# 04_MCU-Part1.net
KiCad netlist of a schematic drawn in Altium Designer
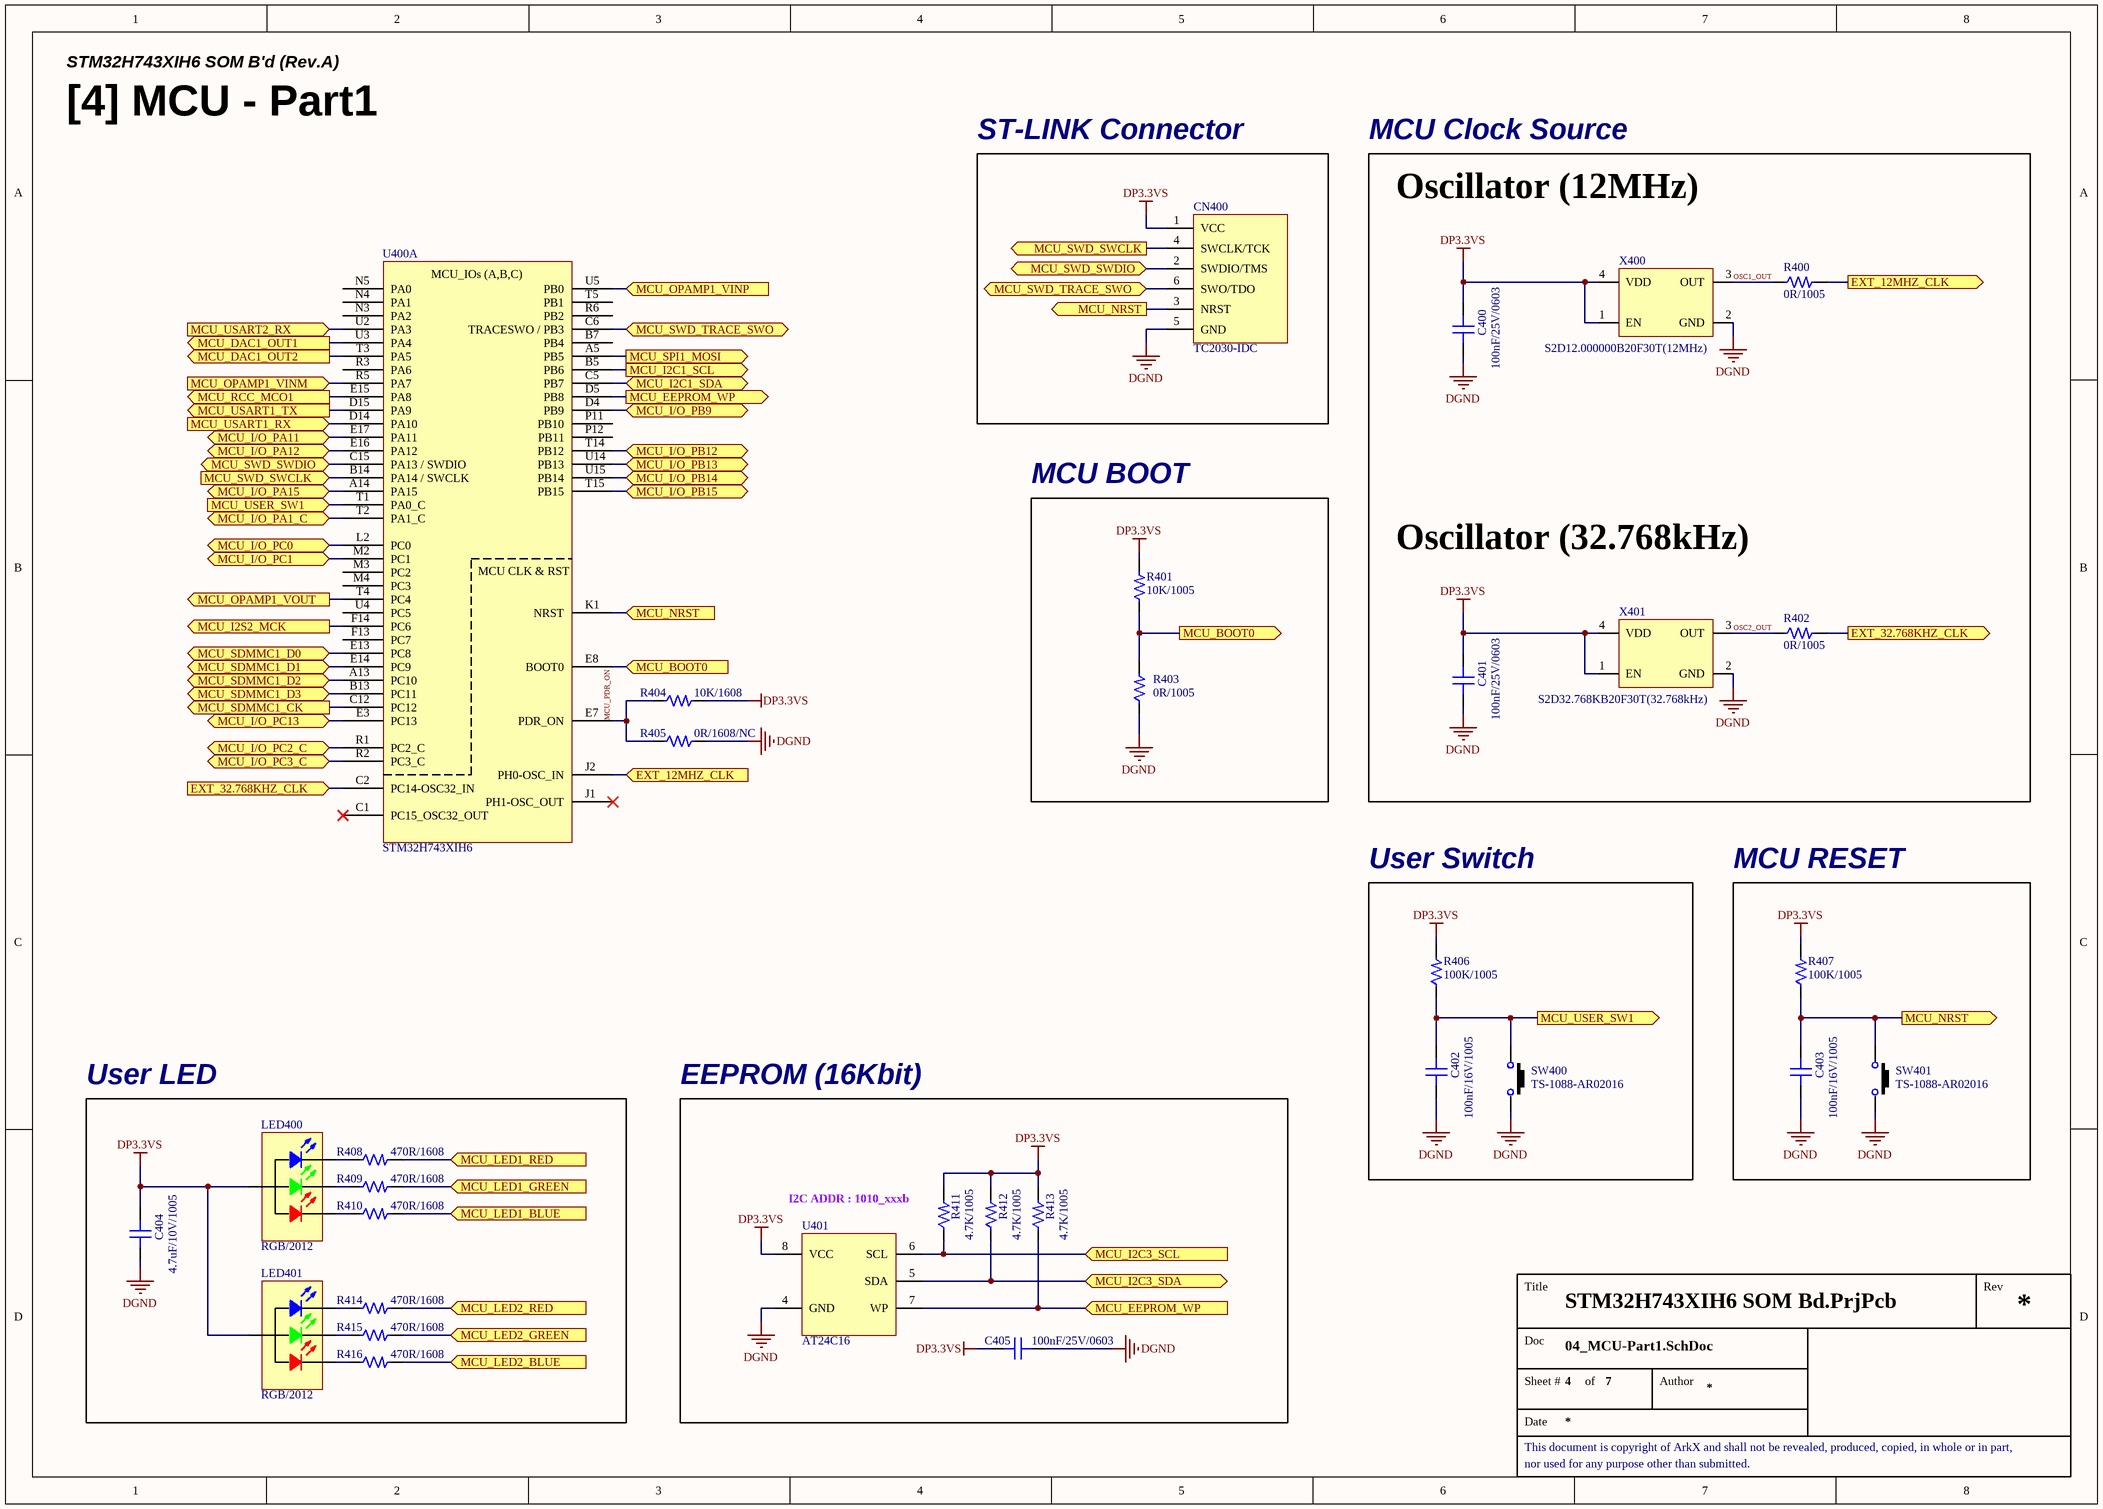
[diagram p0: 04_MCU-Part1.SchDoc]

(export (version "E")
  (design (tool "Eeschema 10.0.6"))
  (components
    (comp (ref "C400")
      (value "100nF/25V/0603")
      (footprint "CAP 0603 (0201_INCH)")
      (description "Ceramic CAP_100nF/25V/0603")
      (fields (field (name "LCSC PART #") "C181047"))
      (libsource (lib "Arkx") (part "CAP_100nF/25V/0603"))
    )
    (comp (ref "C401")
      (value "100nF/25V/0603")
      (footprint "CAP 0603 (0201_INCH)")
      (description "Ceramic CAP_100nF/25V/0603")
      (fields (field (name "LCSC PART #") "C181047"))
      (libsource (lib "Arkx") (part "CAP_100nF/25V/0603"))
    )
    (comp (ref "C402")
      (value "100nF/16V/1005")
      (footprint "CAP 1005 (0402_INCH)")
      (description "Ceramic CAP_100nF/16V/1005")
      (fields (field (name "LCSC PART #") "C1525"))
      (libsource (lib "Arkx") (part "CAP_100nF/16V/1005"))
    )
    (comp (ref "C403")
      (value "100nF/16V/1005")
      (footprint "CAP 1005 (0402_INCH)")
      (description "Ceramic CAP_100nF/16V/1005")
      (fields (field (name "LCSC PART #") "C1525"))
      (libsource (lib "Arkx") (part "CAP_100nF/16V/1005"))
    )
    (comp (ref "C404")
      (value "4.7uF/10V/1005")
      (footprint "CAP 1005 (0402_INCH)")
      (description "10V 4.7uF X5R ±20% 0402  Multilayer Ceramic Capacitors MLCC - SMD/SMT ROHS")
      (fields (field (name "LCSC PART #") "C23733"))
      (libsource (lib "Arkx") (part "CAP_4.7uF/10V/1005"))
    )
    (comp (ref "C405")
      (value "100nF/25V/0603")
      (footprint "CAP 0603 (0201_INCH)")
      (description "Ceramic CAP_100nF/25V/0603")
      (fields (field (name "LCSC PART #") "C181047"))
      (libsource (lib "Arkx") (part "CAP_100nF/25V/0603"))
    )
    (comp (ref "CN400")
      (value "TC2030-IDC")
      (footprint "CON_TC2030-FP")
      (description "Tag-Connect No-Solder SWD Debug Connector DO NOT PLACE")
      (fields (field (name "MANUFACTURER") "Tag-Connect") (field (name "MANUFACTURER PART NUMBER") "TC2030"))
      (libsource (lib "Arkx") (part "CON_TC2030-IDC"))
    )
    (comp (ref "LED400")
      (value "RGB/2012")
      (footprint "LED MHT170RGBCT")
      (fields (field (name "LCSC PART #") "C2962094"))
      (libsource (lib "Arkx") (part "LED_RGB_MHT170RGBCT"))
    )
    (comp (ref "LED401")
      (value "RGB/2012")
      (footprint "LED MHT170RGBCT")
      (fields (field (name "LCSC PART #") "C2962094"))
      (libsource (lib "Arkx") (part "LED_RGB_MHT170RGBCT"))
    )
    (comp (ref "R400")
      (value "0R/1005")
      (footprint "RES 1005 (0402_inch)")
      (description "RES_0R/1005/62.5mW")
      (fields (field (name "LCSC PART #") "C17168"))
      (libsource (lib "Arkx") (part "RES_0R/1005/62.5mW"))
    )
    (comp (ref "R401")
      (value "10K/1005")
      (footprint "RES 1005 (0402_inch)")
      (description "RES_10K/1005/62.5mW")
      (fields (field (name "LCSC PART #") "C25744"))
      (libsource (lib "Arkx") (part "RES_10K/1005/62.5mW"))
    )
    (comp (ref "R402")
      (value "0R/1005")
      (footprint "RES 1005 (0402_inch)")
      (description "RES_0R/1005/62.5mW")
      (fields (field (name "LCSC PART #") "C17168"))
      (libsource (lib "Arkx") (part "RES_0R/1005/62.5mW"))
    )
    (comp (ref "R403")
      (value "0R/1005")
      (footprint "RES 1005 (0402_inch)")
      (description "RES_0R/1005/62.5mW")
      (fields (field (name "LCSC PART #") "C17168"))
      (libsource (lib "Arkx") (part "RES_0R/1005/62.5mW"))
    )
    (comp (ref "R404")
      (value "10K/1608")
      (footprint "RES 1608 (0603_inch)")
      (description "RES_10K/1608/0.1W")
      (fields (field (name "LCSC PART #") "C25804"))
      (libsource (lib "Arkx") (part "RES_10K/1608/0.1W"))
    )
    (comp (ref "R405")
      (value "0R/1608/NC")
      (footprint "RES 1608 (0603_inch)/NC")
      (description "0R/1608/0.1W/NC")
      (libsource (lib "Arkx") (part "RES_NC_0R/1608/0.1W"))
    )
    (comp (ref "R406")
      (value "100K/1005")
      (footprint "RES 1005 (0402_inch)")
      (description "RES_100K/1005/62.5mW")
      (fields (field (name "LCSC PART #") "C25741"))
      (libsource (lib "Arkx") (part "RES_100K/1005/62.5mW"))
    )
    (comp (ref "R407")
      (value "100K/1005")
      (footprint "RES 1005 (0402_inch)")
      (description "RES_100K/1005/62.5mW")
      (fields (field (name "LCSC PART #") "C25741"))
      (libsource (lib "Arkx") (part "RES_100K/1005/62.5mW"))
    )
    (comp (ref "R408")
      (value "470R/1608")
      (footprint "RES 1608 (0603_inch)")
      (description "RES_470R/1608/0.1W")
      (fields (field (name "LCSC PART #") "C23179"))
      (libsource (lib "Arkx") (part "RES_470R/1608/0.1W"))
    )
    (comp (ref "R409")
      (value "470R/1608")
      (footprint "RES 1608 (0603_inch)")
      (description "RES_470R/1608/0.1W")
      (fields (field (name "LCSC PART #") "C23179"))
      (libsource (lib "Arkx") (part "RES_470R/1608/0.1W"))
    )
    (comp (ref "R410")
      (value "470R/1608")
      (footprint "RES 1608 (0603_inch)")
      (description "RES_470R/1608/0.1W")
      (fields (field (name "LCSC PART #") "C23179"))
      (libsource (lib "Arkx") (part "RES_470R/1608/0.1W"))
    )
    (comp (ref "R411")
      (value "4.7K/1005")
      (footprint "RES 1005 (0402_inch)")
      (description "RES_4.7K/1005/62.5mW")
      (fields (field (name "LCSC PART #") "C25900"))
      (libsource (lib "Arkx") (part "RES_4.7K/1005/62.5mW"))
    )
    (comp (ref "R412")
      (value "4.7K/1005")
      (footprint "RES 1005 (0402_inch)")
      (description "RES_4.7K/1005/62.5mW")
      (fields (field (name "LCSC PART #") "C25900"))
      (libsource (lib "Arkx") (part "RES_4.7K/1005/62.5mW"))
    )
    (comp (ref "R413")
      (value "4.7K/1005")
      (footprint "RES 1005 (0402_inch)")
      (description "RES_4.7K/1005/62.5mW")
      (fields (field (name "LCSC PART #") "C25900"))
      (libsource (lib "Arkx") (part "RES_4.7K/1005/62.5mW"))
    )
    (comp (ref "R414")
      (value "470R/1608")
      (footprint "RES 1608 (0603_inch)")
      (description "RES_470R/1608/0.1W")
      (fields (field (name "LCSC PART #") "C23179"))
      (libsource (lib "Arkx") (part "RES_470R/1608/0.1W"))
    )
    (comp (ref "R415")
      (value "470R/1608")
      (footprint "RES 1608 (0603_inch)")
      (description "RES_470R/1608/0.1W")
      (fields (field (name "LCSC PART #") "C23179"))
      (libsource (lib "Arkx") (part "RES_470R/1608/0.1W"))
    )
    (comp (ref "R416")
      (value "470R/1608")
      (footprint "RES 1608 (0603_inch)")
      (description "RES_470R/1608/0.1W")
      (fields (field (name "LCSC PART #") "C23179"))
      (libsource (lib "Arkx") (part "RES_470R/1608/0.1W"))
    )
    (comp (ref "SW400")
      (value "TS-1088-AR02016")
      (footprint "SW_TS-1088-AR02016")
      (description "NO 50mA 100MΩ 100000 Times 12V 160gf@±50gf Brick nogging SPST SMD  Tactile Switches ROHS")
      (fields (field (name "LCSC PART #") "C720477"))
      (libsource (lib "Arkx") (part "SW_TS-1088-AR02016"))
    )
    (comp (ref "SW401")
      (value "TS-1088-AR02016")
      (footprint "SW_TS-1088-AR02016")
      (description "NO 50mA 100MΩ 100000 Times 12V 160gf@±50gf Brick nogging SPST SMD  Tactile Switches ROHS")
      (fields (field (name "LCSC PART #") "C720477"))
      (libsource (lib "Arkx") (part "SW_TS-1088-AR02016"))
    )
    (comp (ref "U400")
      (value "STM32H743XIH6")
      (footprint "IC TFBGA-265")
      (description "ARM® Cortex®-M7 STM32H7 MCU IC 32bit Single-core 480MHz 2MB(2M x 8) Flash 240+25-TFBGA(14x14)")
      (fields (field (name "LCSC PART #") "C114407"))
      (libsource (lib "Arkx") (part "IC_MCU_STM32H743XIH6"))
    )
    (comp (ref "U401")
      (value "AT24C16")
      (footprint "TSSOP-8_PW (TI)")
      (description "IC EEPROM 16KBIT I2C 1MHZ 8TSSOP")
      (fields (field (name "LCSC PART #") "C112954"))
      (libsource (lib "Arkx") (part "IC_EEPROM_AT24C16"))
    )
    (comp (ref "X400")
      (value "S2D12.000000B20F30T(12MHz)")
      (footprint "OSC SMD_2.5x2.0 (SCTF)")
      (description "3.3V~3.3V -40℃~+85℃ 20mA ±20ppm 12MHz SMD2520-4P  Oscillators ROHS")
      (fields (field (name "LCSC PART #") "C387449"))
      (libsource (lib "Arkx") (part "OSC_S2D12.000000B20F30T(12MHz)"))
    )
    (comp (ref "X401")
      (value "S2D32.768KB20F30T(32.768kHz)")
      (footprint "OSC SMD_2.5x2.0 (SCTF)")
      (description "3.3V ±20ppm CMOS 32.768kHz SMD2520-4P  Oscillators ROHS")
      (fields (field (name "LCSC PART #") "C387463"))
      (libsource (lib "Arkx") (part "OSC_S2D32.768KB20F30T(32.768kHz)"))
    )
  )
  (nets
    (net (code "1") (name "/EXT_12MHZ_CLK") (class "Default")
      (node (ref "R400") (pin "2") (pinfunction "2_2") (pintype "passive"))
      (node (ref "U400") (pin "J2") (pinfunction "PH0-OSC_IN_J2") (pintype "passive"))
    )
    (net (code "2") (name "/EXT_32.768KHZ_CLK") (class "Default")
      (node (ref "R402") (pin "2") (pinfunction "2_2") (pintype "passive"))
      (node (ref "U400") (pin "C2") (pinfunction "PC14-OSC32_IN_C2") (pintype "passive"))
    )
    (net (code "3") (name "/MCU_BOOT0") (class "Default")
      (node (ref "R401") (pin "1") (pinfunction "1_1") (pintype "passive"))
      (node (ref "R403") (pin "2") (pinfunction "2_2") (pintype "passive"))
      (node (ref "U400") (pin "E8") (pinfunction "BOOT0_E8") (pintype "passive"))
    )
    (net (code "4") (name "/MCU_DAC1_OUT1") (class "Default")
      (node (ref "U400") (pin "U3") (pinfunction "PA4_U3") (pintype "passive"))
    )
    (net (code "5") (name "/MCU_DAC1_OUT2") (class "Default")
      (node (ref "U400") (pin "T3") (pinfunction "PA5_T3") (pintype "passive"))
    )
    (net (code "6") (name "/MCU_EEPROM_WP") (class "Default")
      (node (ref "R413") (pin "1") (pinfunction "1_1") (pintype "passive"))
      (node (ref "U400") (pin "D5") (pinfunction "PB8_D5") (pintype "passive"))
      (node (ref "U401") (pin "7") (pinfunction "WP_7") (pintype "passive"))
    )
    (net (code "7") (name "/MCU_I2C1_SCL") (class "Default")
      (node (ref "U400") (pin "B5") (pinfunction "PB6_B5") (pintype "passive"))
    )
    (net (code "8") (name "/MCU_I2C1_SDA") (class "Default")
      (node (ref "U400") (pin "C5") (pinfunction "PB7_C5") (pintype "passive"))
    )
    (net (code "9") (name "/MCU_I2C3_SCL") (class "Default")
      (node (ref "R411") (pin "1") (pinfunction "1_1") (pintype "passive"))
      (node (ref "U401") (pin "6") (pinfunction "SCL_6") (pintype "passive"))
    )
    (net (code "10") (name "/MCU_I2C3_SDA") (class "Default")
      (node (ref "R412") (pin "1") (pinfunction "1_1") (pintype "passive"))
      (node (ref "U401") (pin "5") (pinfunction "SDA_5") (pintype "passive"))
    )
    (net (code "11") (name "/MCU_I2S2_MCK") (class "Default")
      (node (ref "U400") (pin "F14") (pinfunction "PC6_F14") (pintype "passive"))
    )
    (net (code "12") (name "/MCU_I{slash}O_PA1_C") (class "Default")
      (node (ref "U400") (pin "T2") (pinfunction "PA1_C_T2") (pintype "passive"))
    )
    (net (code "13") (name "/MCU_I{slash}O_PA11") (class "Default")
      (node (ref "U400") (pin "E17") (pinfunction "PA11_E17") (pintype "passive"))
    )
    (net (code "14") (name "/MCU_I{slash}O_PA12") (class "Default")
      (node (ref "U400") (pin "E16") (pinfunction "PA12_E16") (pintype "passive"))
    )
    (net (code "15") (name "/MCU_I{slash}O_PA15") (class "Default")
      (node (ref "U400") (pin "A14") (pinfunction "PA15_A14") (pintype "passive"))
    )
    (net (code "16") (name "/MCU_I{slash}O_PB9") (class "Default")
      (node (ref "U400") (pin "D4") (pinfunction "PB9_D4") (pintype "passive"))
    )
    (net (code "17") (name "/MCU_I{slash}O_PB12") (class "Default")
      (node (ref "U400") (pin "T14") (pinfunction "PB12_T14") (pintype "passive"))
    )
    (net (code "18") (name "/MCU_I{slash}O_PB13") (class "Default")
      (node (ref "U400") (pin "U14") (pinfunction "PB13_U14") (pintype "passive"))
    )
    (net (code "19") (name "/MCU_I{slash}O_PB14") (class "Default")
      (node (ref "U400") (pin "U15") (pinfunction "PB14_U15") (pintype "passive"))
    )
    (net (code "20") (name "/MCU_I{slash}O_PB15") (class "Default")
      (node (ref "U400") (pin "T15") (pinfunction "PB15_T15") (pintype "passive"))
    )
    (net (code "21") (name "/MCU_I{slash}O_PC0") (class "Default")
      (node (ref "U400") (pin "L2") (pinfunction "PC0_L2") (pintype "passive"))
    )
    (net (code "22") (name "/MCU_I{slash}O_PC1") (class "Default")
      (node (ref "U400") (pin "M2") (pinfunction "PC1_M2") (pintype "passive"))
    )
    (net (code "23") (name "/MCU_I{slash}O_PC2_C") (class "Default")
      (node (ref "U400") (pin "R1") (pinfunction "PC2_C_R1") (pintype "passive"))
    )
    (net (code "24") (name "/MCU_I{slash}O_PC3_C") (class "Default")
      (node (ref "U400") (pin "R2") (pinfunction "PC3_C_R2") (pintype "passive"))
    )
    (net (code "25") (name "/MCU_I{slash}O_PC13") (class "Default")
      (node (ref "U400") (pin "E3") (pinfunction "PC13_E3") (pintype "passive"))
    )
    (net (code "26") (name "/MCU_LED1_BLUE") (class "Default")
      (node (ref "R410") (pin "2") (pinfunction "2_2") (pintype "passive"))
    )
    (net (code "27") (name "/MCU_LED1_GREEN") (class "Default")
      (node (ref "R409") (pin "2") (pinfunction "2_2") (pintype "passive"))
    )
    (net (code "28") (name "/MCU_LED1_RED") (class "Default")
      (node (ref "R408") (pin "2") (pinfunction "2_2") (pintype "passive"))
    )
    (net (code "29") (name "/MCU_LED2_BLUE") (class "Default")
      (node (ref "R416") (pin "2") (pinfunction "2_2") (pintype "passive"))
    )
    (net (code "30") (name "/MCU_LED2_GREEN") (class "Default")
      (node (ref "R415") (pin "2") (pinfunction "2_2") (pintype "passive"))
    )
    (net (code "31") (name "/MCU_LED2_RED") (class "Default")
      (node (ref "R414") (pin "2") (pinfunction "2_2") (pintype "passive"))
    )
    (net (code "32") (name "/MCU_NRST") (class "Default")
      (node (ref "C403") (pin "2") (pinfunction "2_2") (pintype "passive"))
      (node (ref "CN400") (pin "3") (pinfunction "NRST_3") (pintype "passive"))
      (node (ref "R407") (pin "1") (pinfunction "1_1") (pintype "passive"))
      (node (ref "SW401") (pin "1") (pinfunction "1_1") (pintype "passive"))
      (node (ref "U400") (pin "K1") (pinfunction "NRST_K1") (pintype "passive"))
    )
    (net (code "33") (name "/MCU_OPAMP1_VINM") (class "Default")
      (node (ref "U400") (pin "R5") (pinfunction "PA7_R5") (pintype "passive"))
    )
    (net (code "34") (name "/MCU_OPAMP1_VINP") (class "Default")
      (node (ref "U400") (pin "U5") (pinfunction "PB0_U5") (pintype "passive"))
    )
    (net (code "35") (name "/MCU_OPAMP1_VOUT") (class "Default")
      (node (ref "U400") (pin "T4") (pinfunction "PC4_T4") (pintype "passive"))
    )
    (net (code "36") (name "/MCU_PDR_ON") (class "Default")
      (node (ref "R404") (pin "1") (pinfunction "1_1") (pintype "passive"))
      (node (ref "R405") (pin "1") (pinfunction "1_1") (pintype "passive"))
      (node (ref "U400") (pin "E7") (pinfunction "PDR_ON_E7") (pintype "passive"))
    )
    (net (code "37") (name "/MCU_RCC_MCO1") (class "Default")
      (node (ref "U400") (pin "E15") (pinfunction "PA8_E15") (pintype "passive"))
    )
    (net (code "38") (name "/MCU_SDMMC1_CK") (class "Default")
      (node (ref "U400") (pin "C12") (pinfunction "PC12_C12") (pintype "passive"))
    )
    (net (code "39") (name "/MCU_SDMMC1_D0") (class "Default")
      (node (ref "U400") (pin "E13") (pinfunction "PC8_E13") (pintype "passive"))
    )
    (net (code "40") (name "/MCU_SDMMC1_D1") (class "Default")
      (node (ref "U400") (pin "E14") (pinfunction "PC9_E14") (pintype "passive"))
    )
    (net (code "41") (name "/MCU_SDMMC1_D2") (class "Default")
      (node (ref "U400") (pin "A13") (pinfunction "PC10_A13") (pintype "passive"))
    )
    (net (code "42") (name "/MCU_SDMMC1_D3") (class "Default")
      (node (ref "U400") (pin "B13") (pinfunction "PC11_B13") (pintype "passive"))
    )
    (net (code "43") (name "/MCU_SPI1_MOSI") (class "Default")
      (node (ref "U400") (pin "A5") (pinfunction "PB5_A5") (pintype "passive"))
    )
    (net (code "44") (name "/MCU_SWD_SWCLK") (class "Default")
      (node (ref "CN400") (pin "4") (pinfunction "SWCLK/TCK_4") (pintype "passive"))
      (node (ref "U400") (pin "B14") (pinfunction "PA14_/_SWCLK_B14") (pintype "passive"))
    )
    (net (code "45") (name "/MCU_SWD_SWDIO") (class "Default")
      (node (ref "CN400") (pin "2") (pinfunction "SWDIO/TMS_2") (pintype "passive"))
      (node (ref "U400") (pin "C15") (pinfunction "PA13_/_SWDIO_C15") (pintype "passive"))
    )
    (net (code "46") (name "/MCU_SWD_TRACE_SWO") (class "Default")
      (node (ref "CN400") (pin "6") (pinfunction "SWO/TDO_6") (pintype "passive"))
      (node (ref "U400") (pin "C6") (pinfunction "TRACESWO_/_PB3_C6") (pintype "passive"))
    )
    (net (code "47") (name "/MCU_USART1_RX") (class "Default")
      (node (ref "U400") (pin "D14") (pinfunction "PA10_D14") (pintype "passive"))
    )
    (net (code "48") (name "/MCU_USART1_TX") (class "Default")
      (node (ref "U400") (pin "D15") (pinfunction "PA9_D15") (pintype "passive"))
    )
    (net (code "49") (name "/MCU_USART2_RX") (class "Default")
      (node (ref "U400") (pin "U2") (pinfunction "PA3_U2") (pintype "passive"))
    )
    (net (code "50") (name "/MCU_USER_SW1") (class "Default")
      (node (ref "C402") (pin "2") (pinfunction "2_2") (pintype "passive"))
      (node (ref "R406") (pin "1") (pinfunction "1_1") (pintype "passive"))
      (node (ref "SW400") (pin "1") (pinfunction "1_1") (pintype "passive"))
      (node (ref "U400") (pin "T1") (pinfunction "PA0_C_T1") (pintype "passive"))
    )
    (net (code "51") (name "/OSC1_OUT") (class "Default")
      (node (ref "R400") (pin "1") (pinfunction "1_1") (pintype "passive"))
      (node (ref "X400") (pin "3") (pinfunction "OUT_3") (pintype "passive"))
    )
    (net (code "52") (name "/OSC2_OUT") (class "Default")
      (node (ref "R402") (pin "1") (pinfunction "1_1") (pintype "passive"))
      (node (ref "X401") (pin "3") (pinfunction "OUT_3") (pintype "passive"))
    )
    (net (code "53") (name "DGND") (class "Default")
      (node (ref "C400") (pin "2") (pinfunction "2_2") (pintype "passive"))
      (node (ref "C401") (pin "2") (pinfunction "2_2") (pintype "passive"))
      (node (ref "C402") (pin "1") (pinfunction "1_1") (pintype "passive"))
      (node (ref "C403") (pin "1") (pinfunction "1_1") (pintype "passive"))
      (node (ref "C404") (pin "1") (pinfunction "1_1") (pintype "passive"))
      (node (ref "C405") (pin "2") (pinfunction "2_2") (pintype "passive"))
      (node (ref "CN400") (pin "5") (pinfunction "GND_5") (pintype "passive"))
      (node (ref "R403") (pin "1") (pinfunction "1_1") (pintype "passive"))
      (node (ref "R405") (pin "2") (pinfunction "2_2") (pintype "passive"))
      (node (ref "SW400") (pin "2") (pinfunction "2_2") (pintype "passive"))
      (node (ref "SW401") (pin "2") (pinfunction "2_2") (pintype "passive"))
      (node (ref "U401") (pin "4") (pinfunction "GND_4") (pintype "passive"))
      (node (ref "X400") (pin "2") (pinfunction "GND_2") (pintype "passive"))
      (node (ref "X401") (pin "2") (pinfunction "GND_2") (pintype "passive"))
    )
    (net (code "54") (name "DP3.3VS") (class "Default")
      (node (ref "C400") (pin "1") (pinfunction "1_1") (pintype "passive"))
      (node (ref "C401") (pin "1") (pinfunction "1_1") (pintype "passive"))
      (node (ref "C404") (pin "2") (pinfunction "2_2") (pintype "passive"))
      (node (ref "C405") (pin "1") (pinfunction "1_1") (pintype "passive"))
      (node (ref "CN400") (pin "1") (pinfunction "VCC_1") (pintype "passive"))
      (node (ref "LED400") (pin "4") (pinfunction "Common_Anode_4") (pintype "passive"))
      (node (ref "LED401") (pin "4") (pinfunction "Common_Anode_4") (pintype "passive"))
      (node (ref "R401") (pin "2") (pinfunction "2_2") (pintype "passive"))
      (node (ref "R404") (pin "2") (pinfunction "2_2") (pintype "passive"))
      (node (ref "R406") (pin "2") (pinfunction "2_2") (pintype "passive"))
      (node (ref "R407") (pin "2") (pinfunction "2_2") (pintype "passive"))
      (node (ref "R411") (pin "2") (pinfunction "2_2") (pintype "passive"))
      (node (ref "R412") (pin "2") (pinfunction "2_2") (pintype "passive"))
      (node (ref "R413") (pin "2") (pinfunction "2_2") (pintype "passive"))
      (node (ref "U401") (pin "8") (pinfunction "VCC_8") (pintype "passive"))
      (node (ref "X400") (pin "1") (pinfunction "EN_1") (pintype "passive"))
      (node (ref "X400") (pin "4") (pinfunction "VDD_4") (pintype "passive"))
      (node (ref "X401") (pin "1") (pinfunction "EN_1") (pintype "passive"))
      (node (ref "X401") (pin "4") (pinfunction "VDD_4") (pintype "passive"))
    )
    (net (code "55") (name "Net-(LED400-BLUE)") (class "Default")
      (node (ref "LED400") (pin "3") (pinfunction "BLUE_3") (pintype "passive"))
      (node (ref "R408") (pin "1") (pinfunction "1_1") (pintype "passive"))
    )
    (net (code "56") (name "Net-(LED400-GREEN)") (class "Default")
      (node (ref "LED400") (pin "2") (pinfunction "GREEN_2") (pintype "passive"))
      (node (ref "R409") (pin "1") (pinfunction "1_1") (pintype "passive"))
    )
    (net (code "57") (name "Net-(LED400-RED)") (class "Default")
      (node (ref "LED400") (pin "1") (pinfunction "RED_1") (pintype "passive"))
      (node (ref "R410") (pin "1") (pinfunction "1_1") (pintype "passive"))
    )
    (net (code "58") (name "Net-(LED401-BLUE)") (class "Default")
      (node (ref "LED401") (pin "3") (pinfunction "BLUE_3") (pintype "passive"))
      (node (ref "R414") (pin "1") (pinfunction "1_1") (pintype "passive"))
    )
    (net (code "59") (name "Net-(LED401-GREEN)") (class "Default")
      (node (ref "LED401") (pin "2") (pinfunction "GREEN_2") (pintype "passive"))
      (node (ref "R415") (pin "1") (pinfunction "1_1") (pintype "passive"))
    )
    (net (code "60") (name "Net-(LED401-RED)") (class "Default")
      (node (ref "LED401") (pin "1") (pinfunction "RED_1") (pintype "passive"))
      (node (ref "R416") (pin "1") (pinfunction "1_1") (pintype "passive"))
    )
    (net (code "61") (name "unconnected-(U400A-PA0-PadN5)") (class "Default")
      (node (ref "U400") (pin "N5") (pinfunction "PA0_N5") (pintype "passive"))
    )
    (net (code "62") (name "unconnected-(U400A-PA1-PadN4)") (class "Default")
      (node (ref "U400") (pin "N4") (pinfunction "PA1_N4") (pintype "passive"))
    )
    (net (code "63") (name "unconnected-(U400A-PA2-PadN3)") (class "Default")
      (node (ref "U400") (pin "N3") (pinfunction "PA2_N3") (pintype "passive"))
    )
    (net (code "64") (name "unconnected-(U400A-PA6-PadR3)") (class "Default")
      (node (ref "U400") (pin "R3") (pinfunction "PA6_R3") (pintype "passive"))
    )
    (net (code "65") (name "unconnected-(U400A-PB1-PadT5)") (class "Default")
      (node (ref "U400") (pin "T5") (pinfunction "PB1_T5") (pintype "passive"))
    )
    (net (code "66") (name "unconnected-(U400A-PB2-PadR6)") (class "Default")
      (node (ref "U400") (pin "R6") (pinfunction "PB2_R6") (pintype "passive"))
    )
    (net (code "67") (name "unconnected-(U400A-PB4-PadB7)") (class "Default")
      (node (ref "U400") (pin "B7") (pinfunction "PB4_B7") (pintype "passive"))
    )
    (net (code "68") (name "unconnected-(U400A-PB10-PadP11)") (class "Default")
      (node (ref "U400") (pin "P11") (pinfunction "PB10_P11") (pintype "passive"))
    )
    (net (code "69") (name "unconnected-(U400A-PB11-PadP12)") (class "Default")
      (node (ref "U400") (pin "P12") (pinfunction "PB11_P12") (pintype "passive"))
    )
    (net (code "70") (name "unconnected-(U400A-PC2-PadM3)") (class "Default")
      (node (ref "U400") (pin "M3") (pinfunction "PC2_M3") (pintype "passive"))
    )
    (net (code "71") (name "unconnected-(U400A-PC3-PadM4)") (class "Default")
      (node (ref "U400") (pin "M4") (pinfunction "PC3_M4") (pintype "passive"))
    )
    (net (code "72") (name "unconnected-(U400A-PC5-PadU4)") (class "Default")
      (node (ref "U400") (pin "U4") (pinfunction "PC5_U4") (pintype "passive"))
    )
    (net (code "73") (name "unconnected-(U400A-PC7-PadF13)") (class "Default")
      (node (ref "U400") (pin "F13") (pinfunction "PC7_F13") (pintype "passive"))
    )
    (net (code "74") (name "unconnected-(U400A-PC15_OSC32_OUT-PadC1)") (class "Default")
      (node (ref "U400") (pin "C1") (pinfunction "PC15_OSC32_OUT_C1") (pintype "passive+no_connect"))
    )
    (net (code "75") (name "unconnected-(U400A-PH1-OSC_OUT-PadJ1)") (class "Default")
      (node (ref "U400") (pin "J1") (pinfunction "PH1-OSC_OUT_J1") (pintype "passive+no_connect"))
    )
  )
)
